# LB_BIT_oX_1IN_1OUT-SMALL-v03_1_1x.net
KiCad netlist of a schematic drawn in EAGLE
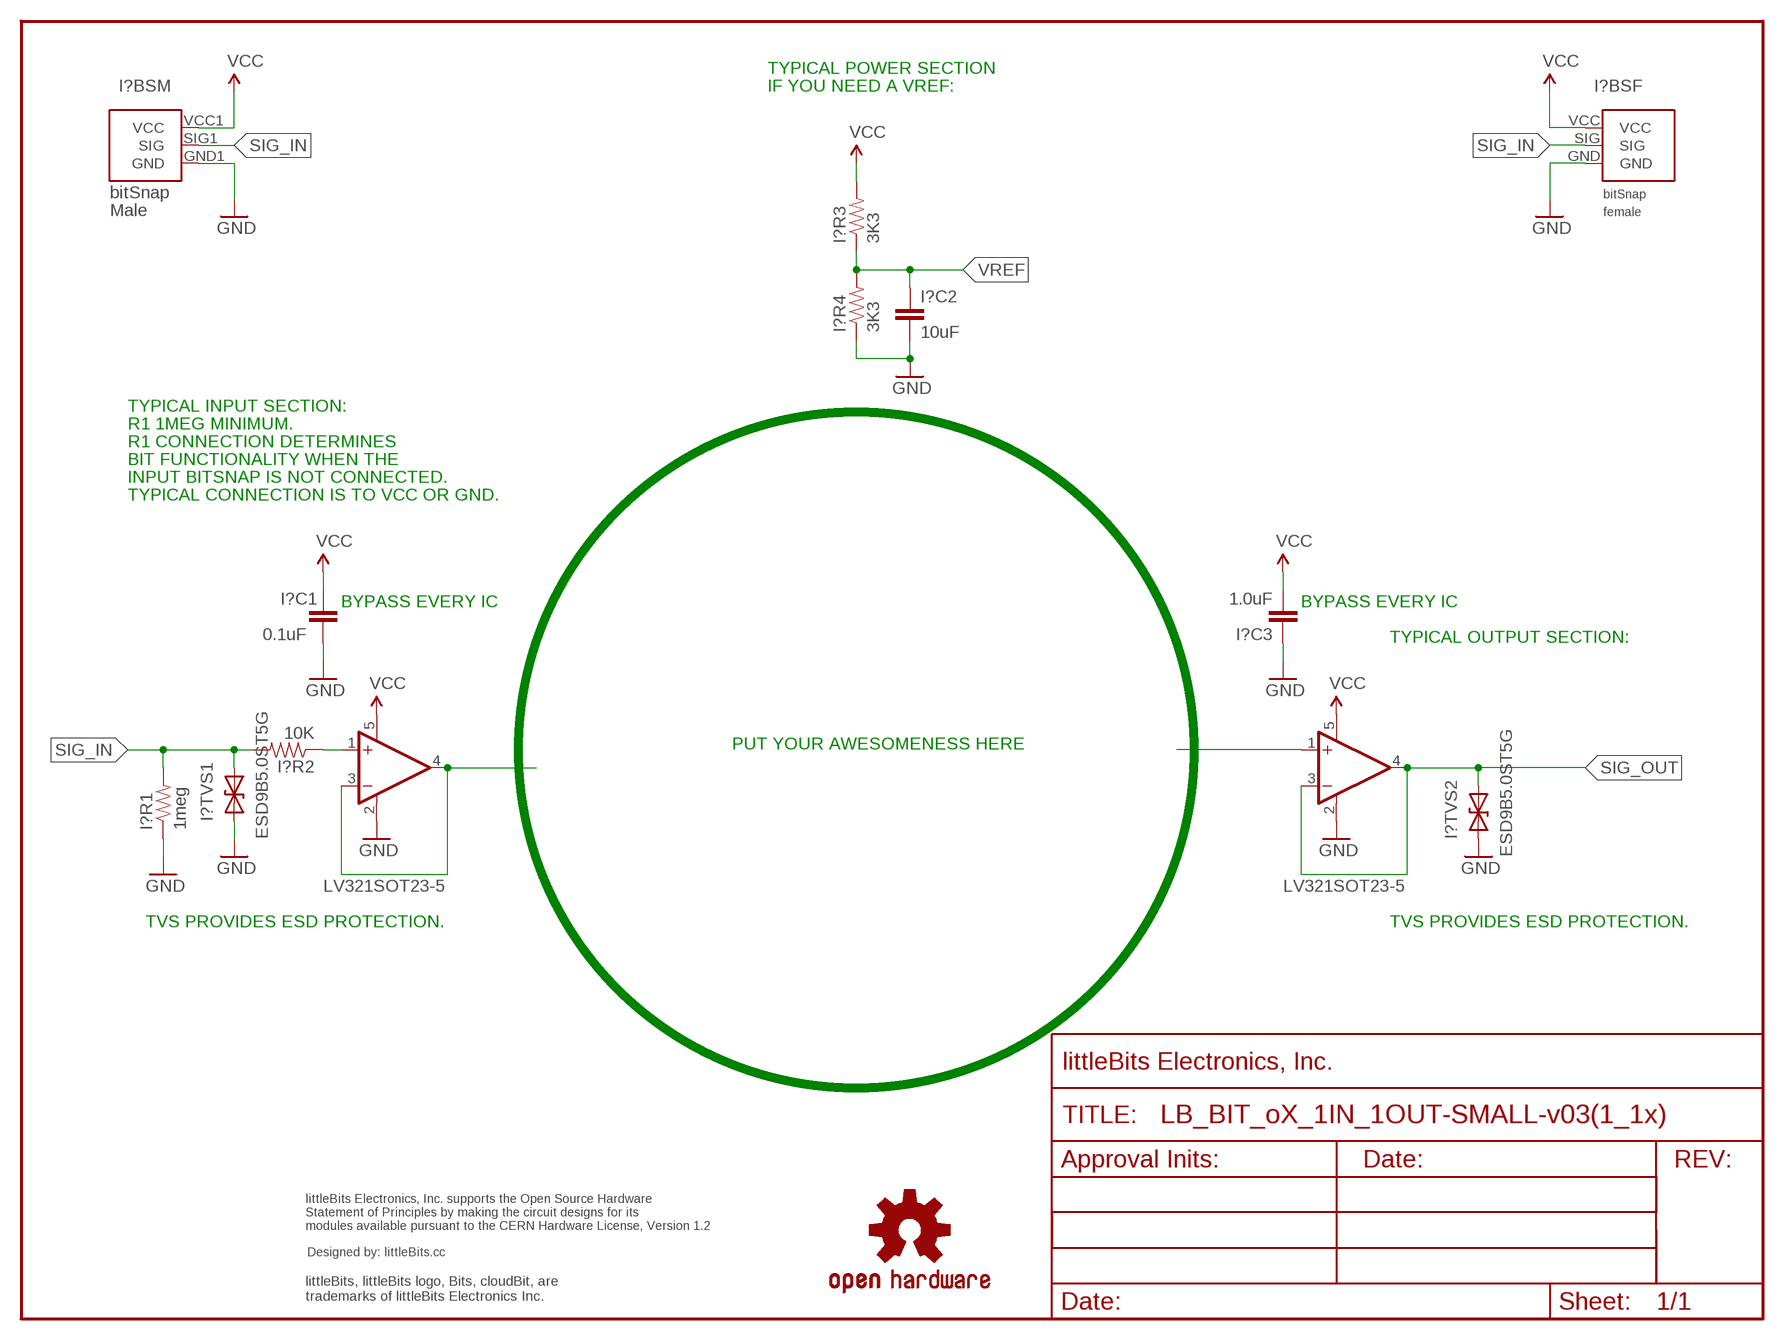
[diagram p0: schematic, sheet 1]

(export (version "E")
  (design (tool "Eeschema 10.0.6"))
  (components
    (comp (ref "I?BSF")
      (value "BITSNAP_V03_FEMALE")
      (footprint "eagle-import:BITSNAP_V03_FEMALE")
      (libsource (lib "eagle-import") (part "BITSNAP_V03_FEMALE"))
    )
    (comp (ref "I?BSM")
      (value "BITSNAP_V03_MALE")
      (footprint "eagle-import:BITSNAP_V03_MALE")
      (libsource (lib "eagle-import") (part "BITSNAP_V03_MALE"))
    )
    (comp (ref "I?C1")
      (value "0.1uF")
      (footprint "eagle-import:CAP-0603")
      (libsource (lib "eagle-import") (part "CAPCAP-0603"))
    )
    (comp (ref "I?C2")
      (value "10uF")
      (footprint "eagle-import:CAP-0603")
      (libsource (lib "eagle-import") (part "CAPCAP-0603"))
    )
    (comp (ref "I?C3")
      (value "1.0uF")
      (footprint "eagle-import:CAP-0603")
      (libsource (lib "eagle-import") (part "CAPCAP-0603"))
    )
    (comp (ref "I?R1")
      (value "1meg")
      (footprint "eagle-import:RES-0603")
      (libsource (lib "eagle-import") (part "RESISTOR0603"))
    )
    (comp (ref "I?R2")
      (value "10K")
      (footprint "eagle-import:RES-0603")
      (libsource (lib "eagle-import") (part "RESISTOR0603"))
    )
    (comp (ref "I?R3")
      (value "3K3")
      (footprint "eagle-import:RES-0603")
      (libsource (lib "eagle-import") (part "RESISTOR0603"))
    )
    (comp (ref "I?R4")
      (value "3K3")
      (footprint "eagle-import:RES-0603")
      (libsource (lib "eagle-import") (part "RESISTOR0603"))
    )
    (comp (ref "I?TVS1")
      (value "ESD9B5.0ST5G")
      (footprint "eagle-import:SOD-923")
      (libsource (lib "eagle-import") (part "DIODE-TVSSOD-923"))
    )
    (comp (ref "I?TVS2")
      (value "ESD9B5.0ST5G")
      (footprint "eagle-import:SOD-923")
      (libsource (lib "eagle-import") (part "DIODE-TVSSOD-923"))
    )
    (comp (ref "U$1")
      (value "OSHWCREDIT")
      (footprint "eagle-import:OSHWCREDIT")
      (libsource (lib "eagle-import") (part "OSHWCREDIT"))
    )
    (comp (ref "U$2")
      (value "OSHW-LOGOL")
      (footprint "eagle-import:OSHW-LOGO-L")
      (libsource (lib "eagle-import") (part "OSHW-LOGOL"))
    )
    (comp (ref "U$3")
      (value "FRAME-LETTER")
      (footprint "eagle-import:FABDWG01-OHW")
      (libsource (lib "eagle-import") (part "FRAME-LETTER"))
    )
    (comp (ref "U1")
      (value "LV321SOT23-5")
      (footprint "eagle-import:SOT23-5")
      (libsource (lib "eagle-import") (part "LV321SOT23-5"))
    )
    (comp (ref "U2")
      (value "LV321SOT23-5")
      (footprint "eagle-import:SOT23-5")
      (libsource (lib "eagle-import") (part "LV321SOT23-5"))
    )
  )
  (nets
    (net (code "1") (name "GND") (class "Default")
      (node (ref "I?BSF") (pin "GND") (pinfunction "GND_GND") (pintype "bidirectional"))
      (node (ref "I?BSM") (pin "GND1") (pinfunction "GND_GND1") (pintype "bidirectional"))
      (node (ref "I?C1") (pin "2") (pinfunction "2_2") (pintype "passive"))
      (node (ref "I?C2") (pin "2") (pinfunction "2_2") (pintype "passive"))
      (node (ref "I?C3") (pin "1") (pinfunction "1_1") (pintype "passive"))
      (node (ref "I?R1") (pin "1") (pinfunction "1_1") (pintype "passive"))
      (node (ref "I?R4") (pin "1") (pinfunction "1_1") (pintype "passive"))
      (node (ref "I?TVS1") (pin "1") (pinfunction "A_1") (pintype "passive"))
      (node (ref "I?TVS2") (pin "1") (pinfunction "A_1") (pintype "passive"))
      (node (ref "U1") (pin "2") (pinfunction "V-_2") (pintype "power_in"))
      (node (ref "U2") (pin "2") (pinfunction "V-_2") (pintype "power_in"))
    )
    (net (code "2") (name "Net-(U1-+IN)") (class "Default")
      (node (ref "I?R2") (pin "1") (pinfunction "1_1") (pintype "passive"))
      (node (ref "U1") (pin "1") (pinfunction "+IN_1") (pintype "input"))
    )
    (net (code "3") (name "Net-(U1--IN)") (class "Default")
      (node (ref "U1") (pin "3") (pinfunction "-IN_3") (pintype "input"))
      (node (ref "U1") (pin "4") (pinfunction "OUT_4") (pintype "output"))
    )
    (net (code "4") (name "SIG_IN") (class "Default")
      (node (ref "I?BSF") (pin "SIG") (pinfunction "SIG_SIG") (pintype "bidirectional"))
      (node (ref "I?BSM") (pin "SIG1") (pinfunction "SIG_SIG1") (pintype "bidirectional"))
      (node (ref "I?R1") (pin "2") (pinfunction "2_2") (pintype "passive"))
      (node (ref "I?R2") (pin "2") (pinfunction "2_2") (pintype "passive"))
      (node (ref "I?TVS1") (pin "2") (pinfunction "C_2") (pintype "passive"))
    )
    (net (code "5") (name "SIG_OUT") (class "Default")
      (node (ref "I?TVS2") (pin "2") (pinfunction "C_2") (pintype "passive"))
      (node (ref "U2") (pin "3") (pinfunction "-IN_3") (pintype "input"))
      (node (ref "U2") (pin "4") (pinfunction "OUT_4") (pintype "output"))
    )
    (net (code "6") (name "VCC") (class "Default")
      (node (ref "I?BSF") (pin "VCC") (pinfunction "VCC_VCC") (pintype "bidirectional"))
      (node (ref "I?BSM") (pin "VCC1") (pinfunction "VCC_VCC1") (pintype "bidirectional"))
      (node (ref "I?C1") (pin "1") (pinfunction "1_1") (pintype "passive"))
      (node (ref "I?C3") (pin "2") (pinfunction "2_2") (pintype "passive"))
      (node (ref "I?R3") (pin "2") (pinfunction "2_2") (pintype "passive"))
      (node (ref "U1") (pin "5") (pinfunction "V+_5") (pintype "power_in"))
      (node (ref "U2") (pin "5") (pinfunction "V+_5") (pintype "power_in"))
    )
    (net (code "7") (name "VREF") (class "Default")
      (node (ref "I?C2") (pin "1") (pinfunction "1_1") (pintype "passive"))
      (node (ref "I?R3") (pin "1") (pinfunction "1_1") (pintype "passive"))
      (node (ref "I?R4") (pin "2") (pinfunction "2_2") (pintype "passive"))
    )
    (net (code "8") (name "unconnected-(U2-+IN-Pad1)") (class "Default")
      (node (ref "U2") (pin "1") (pinfunction "+IN_1") (pintype "input"))
    )
  )
)
